# S7CAS-PLEIADES-CARTE-MERE_P20_Mechanical.net
KiCad netlist of a schematic drawn in Altium Designer
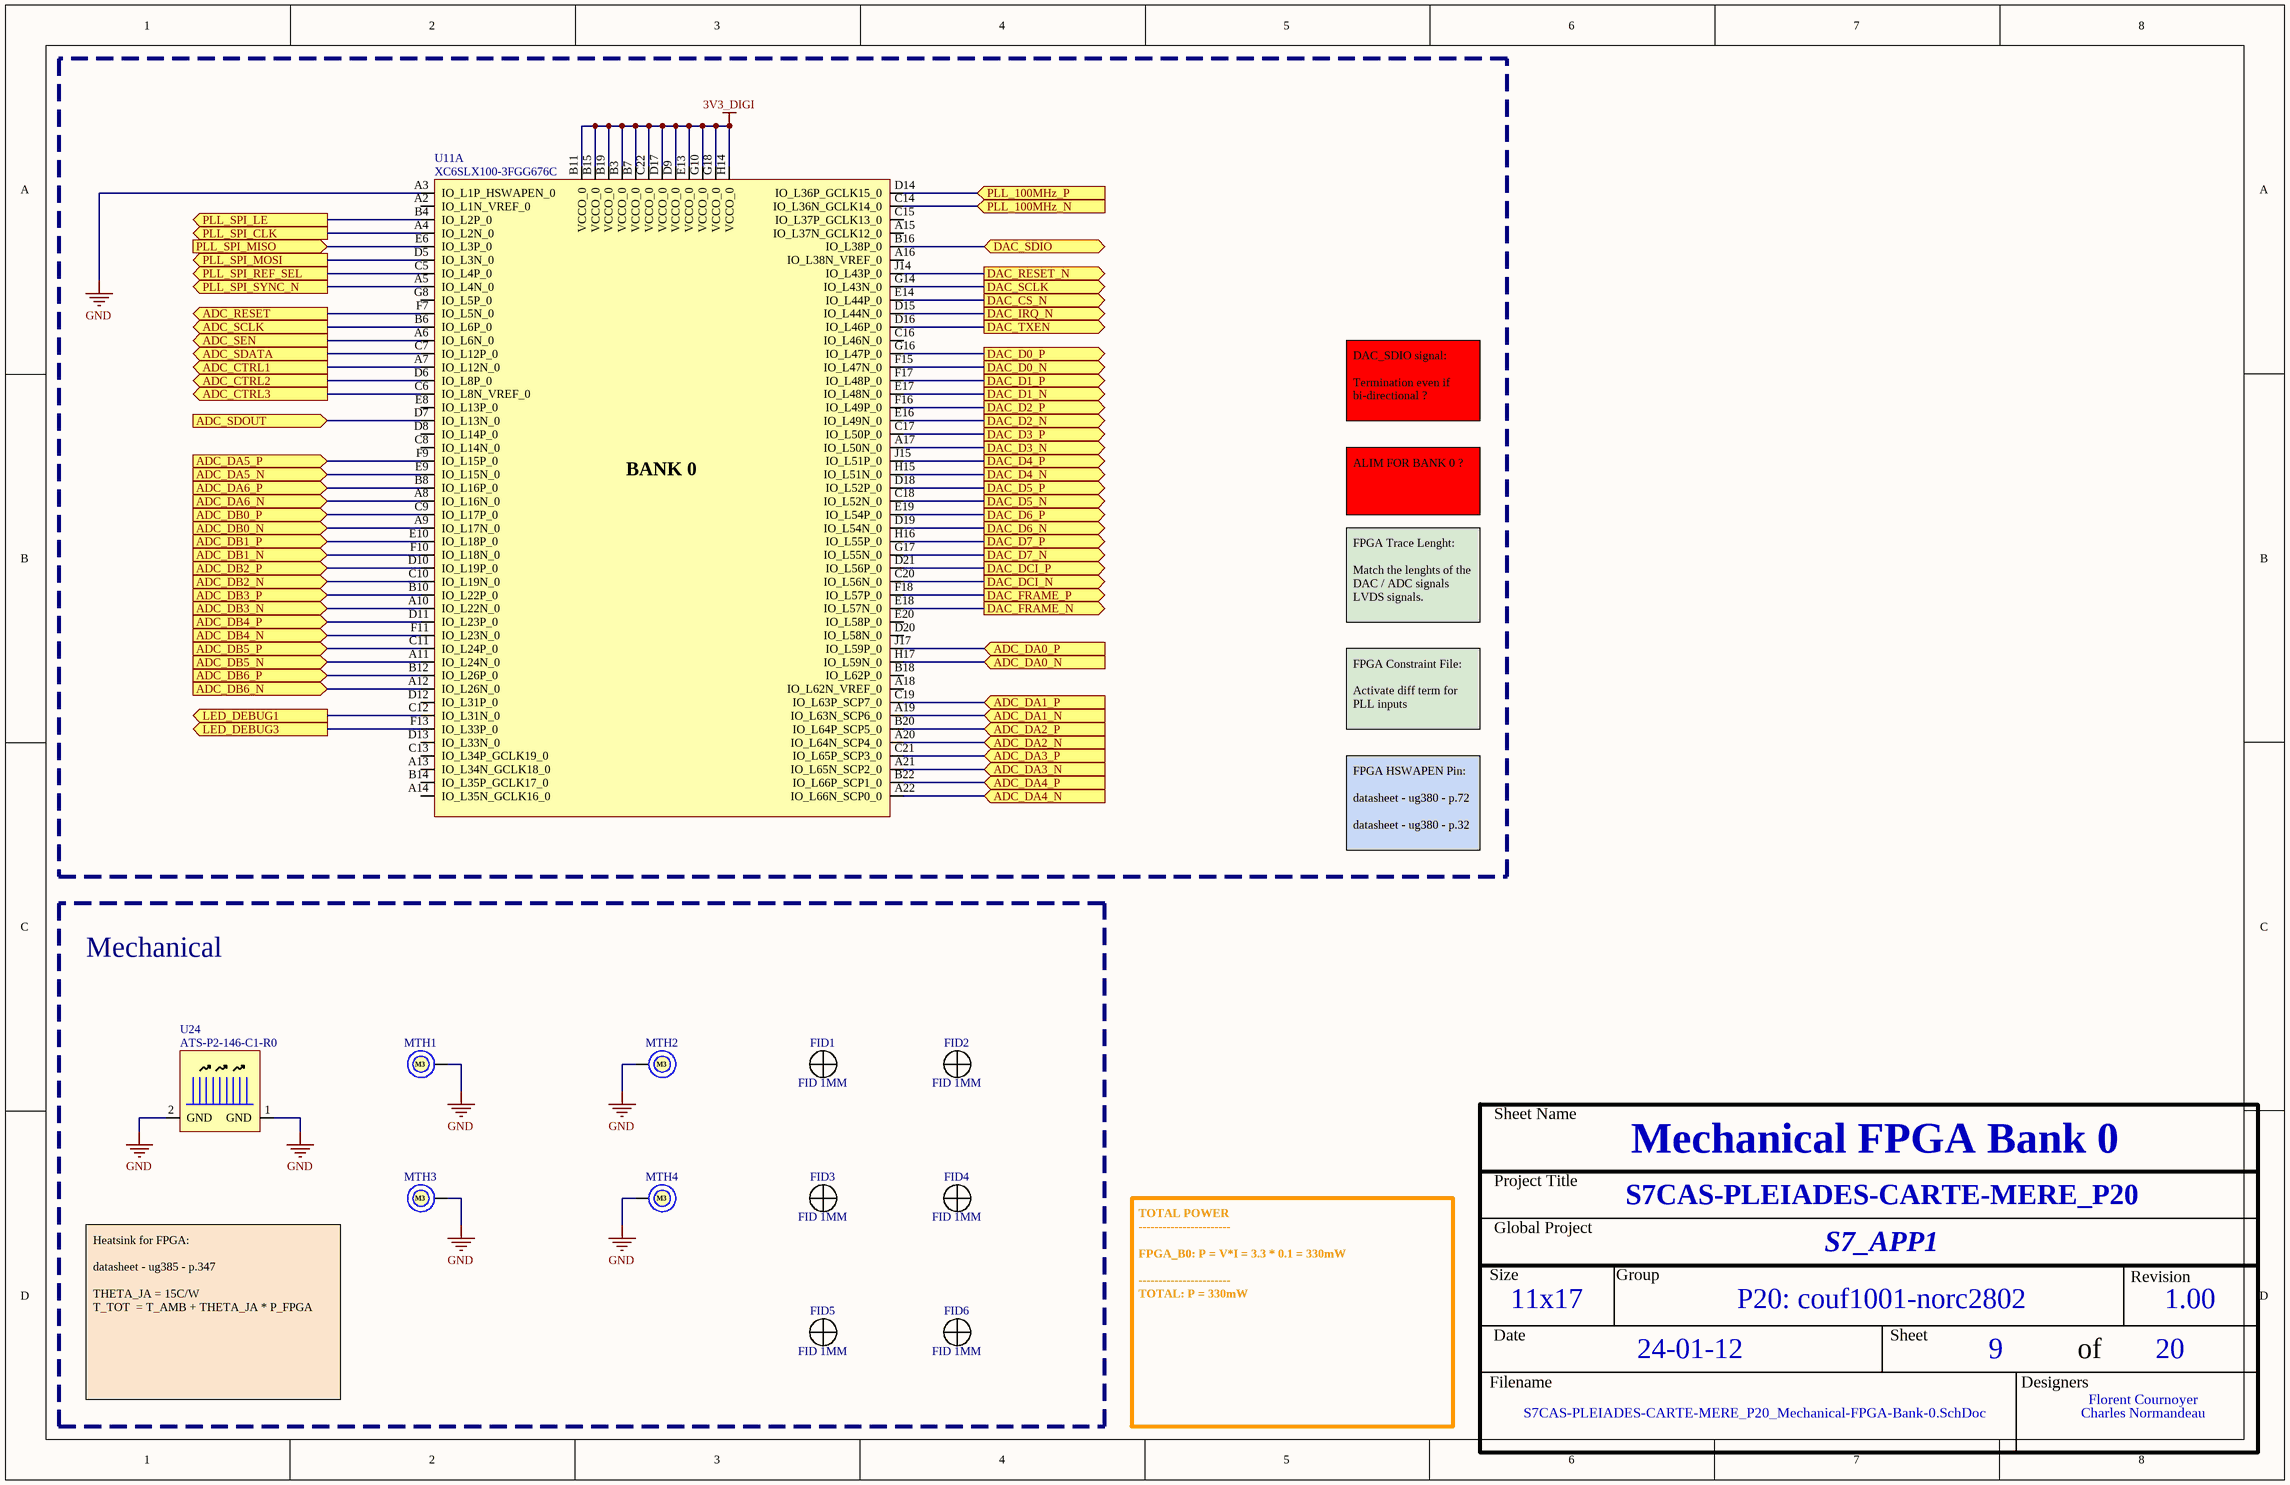
[diagram p0: S7CAS-PLEIADES-CARTE-MERE_P20_Mechanical-FPGA-Bank-0.SchDoc]

(export (version "E")
  (design (tool "Eeschema 10.0.6"))
  (components
    (comp (ref "FID1")
      (value "FID 1MM")
      (footprint "FID_CIRCLE_1MM")
      (description "FID - FIDUCIAL 1MM CIRCLE DOUBLE-SIDED - 1MM")
      (fields
        (field (name "CREATEDBY/DATE") "Jonathan Bouchard 2018-07-23")
        (field (name "VERIFIEDBY") "Caroline Paulin - 25 juillet 2018")
      )
      (libsource (lib "S7CAS_LIB2023") (part "FID_CIRCLE_1MM"))
    )
    (comp (ref "FID2")
      (value "FID 1MM")
      (footprint "FID_CIRCLE_1MM")
      (description "FID - FIDUCIAL 1MM CIRCLE DOUBLE-SIDED - 1MM")
      (fields
        (field (name "CREATEDBY/DATE") "Jonathan Bouchard 2018-07-23")
        (field (name "VERIFIEDBY") "Caroline Paulin - 25 juillet 2018")
      )
      (libsource (lib "S7CAS_LIB2023") (part "FID_CIRCLE_1MM"))
    )
    (comp (ref "FID3")
      (value "FID 1MM")
      (footprint "FID_CIRCLE_1MM")
      (description "FID - FIDUCIAL 1MM CIRCLE DOUBLE-SIDED - 1MM")
      (fields
        (field (name "CREATEDBY/DATE") "Jonathan Bouchard 2018-07-23")
        (field (name "VERIFIEDBY") "Caroline Paulin - 25 juillet 2018")
      )
      (libsource (lib "S7CAS_LIB2023") (part "FID_CIRCLE_1MM"))
    )
    (comp (ref "FID4")
      (value "FID 1MM")
      (footprint "FID_CIRCLE_1MM")
      (description "FID - FIDUCIAL 1MM CIRCLE DOUBLE-SIDED - 1MM")
      (fields
        (field (name "CREATEDBY/DATE") "Jonathan Bouchard 2018-07-23")
        (field (name "VERIFIEDBY") "Caroline Paulin - 25 juillet 2018")
      )
      (libsource (lib "S7CAS_LIB2023") (part "FID_CIRCLE_1MM"))
    )
    (comp (ref "FID5")
      (value "FID 1MM")
      (footprint "FID_CIRCLE_1MM")
      (description "FID - FIDUCIAL 1MM CIRCLE DOUBLE-SIDED - 1MM")
      (fields
        (field (name "CREATEDBY/DATE") "Jonathan Bouchard 2018-07-23")
        (field (name "VERIFIEDBY") "Caroline Paulin - 25 juillet 2018")
      )
      (libsource (lib "S7CAS_LIB2023") (part "FID_CIRCLE_1MM"))
    )
    (comp (ref "FID6")
      (value "FID 1MM")
      (footprint "FID_CIRCLE_1MM")
      (description "FID - FIDUCIAL 1MM CIRCLE DOUBLE-SIDED - 1MM")
      (fields
        (field (name "CREATEDBY/DATE") "Jonathan Bouchard 2018-07-23")
        (field (name "VERIFIEDBY") "Caroline Paulin - 25 juillet 2018")
      )
      (libsource (lib "S7CAS_LIB2023") (part "FID_CIRCLE_1MM"))
    )
    (comp (ref "MTH1")
      (value "M3")
      (footprint "MTH_M3")
      (description "MTH - MOUNTING HOLE M3 PLATED - M3")
      (fields
        (field (name "CREATEDBY/DATE") "Jonathan Bouchard 2018-07-23")
        (field (name "VERIFIEDBY") "Arnaud Samson 23-07-18")
      )
      (libsource (lib "S7CAS_LIB2023") (part "MTH_M3"))
    )
    (comp (ref "MTH2")
      (value "M3")
      (footprint "MTH_M3")
      (description "MTH - MOUNTING HOLE M3 PLATED - M3")
      (fields
        (field (name "CREATEDBY/DATE") "Jonathan Bouchard 2018-07-23")
        (field (name "VERIFIEDBY") "Arnaud Samson 23-07-18")
      )
      (libsource (lib "S7CAS_LIB2023") (part "MTH_M3"))
    )
    (comp (ref "MTH3")
      (value "M3")
      (footprint "MTH_M3")
      (description "MTH - MOUNTING HOLE M3 PLATED - M3")
      (fields
        (field (name "CREATEDBY/DATE") "Jonathan Bouchard 2018-07-23")
        (field (name "VERIFIEDBY") "Arnaud Samson 23-07-18")
      )
      (libsource (lib "S7CAS_LIB2023") (part "MTH_M3"))
    )
    (comp (ref "MTH4")
      (value "M3")
      (footprint "MTH_M3")
      (description "MTH - MOUNTING HOLE M3 PLATED - M3")
      (fields
        (field (name "CREATEDBY/DATE") "Jonathan Bouchard 2018-07-23")
        (field (name "VERIFIEDBY") "Arnaud Samson 23-07-18")
      )
      (libsource (lib "S7CAS_LIB2023") (part "MTH_M3"))
    )
    (comp (ref "U11")
      (value "XC6SLX100-3FGG676C")
      (footprint "FPGA_XILINX_FGG676")
      (description "FPGA - XILINX SPARTAN 6 480 I/O - BGA-676")
      (fields
        (field (name "VOLTAGE") "1.14 V ~ 1.26 V")
        (field (name "MFG") "Xilinx")
        (field (name "CREATEDBY") "Jonathan Bouchard")
      )
      (libsource (lib "S7CAS_LIB2023") (part "FPGA_XC6SLX100-3FGG676C"))
    )
    (comp (ref "U24")
      (value "ATS-P2-146-C1-R0")
      (footprint "HEATSINK")
      (description "HEATSINK 30X30X35MM L-TAB")
      (libsource (lib "LIB_TEMP_P20_CHARLES_NORMANDEAU_SCH") (part "HEATSINK"))
    )
  )
  (nets
    (net (code "1") (name "/ADC_CTRL1") (class "Default")
      (node (ref "U11") (pin "A7") (pinfunction "IO_L12N_0_A7") (pintype "passive"))
    )
    (net (code "2") (name "/ADC_CTRL2") (class "Default")
      (node (ref "U11") (pin "D6") (pinfunction "IO_L8P_0_D6") (pintype "passive"))
    )
    (net (code "3") (name "/ADC_CTRL3") (class "Default")
      (node (ref "U11") (pin "C6") (pinfunction "IO_L8N_VREF_0_C6") (pintype "passive"))
    )
    (net (code "4") (name "/ADC_DA0_N") (class "Default")
      (node (ref "U11") (pin "H17") (pinfunction "IO_L59N_0_H17") (pintype "passive"))
    )
    (net (code "5") (name "/ADC_DA0_P") (class "Default")
      (node (ref "U11") (pin "J17") (pinfunction "IO_L59P_0_J17") (pintype "passive"))
    )
    (net (code "6") (name "/ADC_DA1_N") (class "Default")
      (node (ref "U11") (pin "A19") (pinfunction "IO_L63N_SCP6_0_A19") (pintype "passive"))
    )
    (net (code "7") (name "/ADC_DA1_P") (class "Default")
      (node (ref "U11") (pin "C19") (pinfunction "IO_L63P_SCP7_0_C19") (pintype "passive"))
    )
    (net (code "8") (name "/ADC_DA2_N") (class "Default")
      (node (ref "U11") (pin "A20") (pinfunction "IO_L64N_SCP4_0_A20") (pintype "passive"))
    )
    (net (code "9") (name "/ADC_DA2_P") (class "Default")
      (node (ref "U11") (pin "B20") (pinfunction "IO_L64P_SCP5_0_B20") (pintype "passive"))
    )
    (net (code "10") (name "/ADC_DA3_N") (class "Default")
      (node (ref "U11") (pin "A21") (pinfunction "IO_L65N_SCP2_0_A21") (pintype "passive"))
    )
    (net (code "11") (name "/ADC_DA3_P") (class "Default")
      (node (ref "U11") (pin "C21") (pinfunction "IO_L65P_SCP3_0_C21") (pintype "passive"))
    )
    (net (code "12") (name "/ADC_DA4_N") (class "Default")
      (node (ref "U11") (pin "A22") (pinfunction "IO_L66N_SCP0_0_A22") (pintype "passive"))
    )
    (net (code "13") (name "/ADC_DA4_P") (class "Default")
      (node (ref "U11") (pin "B22") (pinfunction "IO_L66P_SCP1_0_B22") (pintype "passive"))
    )
    (net (code "14") (name "/ADC_DA5_N") (class "Default")
      (node (ref "U11") (pin "E9") (pinfunction "IO_L15N_0_E9") (pintype "passive"))
    )
    (net (code "15") (name "/ADC_DA5_P") (class "Default")
      (node (ref "U11") (pin "F9") (pinfunction "IO_L15P_0_F9") (pintype "passive"))
    )
    (net (code "16") (name "/ADC_DA6_N") (class "Default")
      (node (ref "U11") (pin "A8") (pinfunction "IO_L16N_0_A8") (pintype "passive"))
    )
    (net (code "17") (name "/ADC_DA6_P") (class "Default")
      (node (ref "U11") (pin "B8") (pinfunction "IO_L16P_0_B8") (pintype "passive"))
    )
    (net (code "18") (name "/ADC_DB0_N") (class "Default")
      (node (ref "U11") (pin "A9") (pinfunction "IO_L17N_0_A9") (pintype "passive"))
    )
    (net (code "19") (name "/ADC_DB0_P") (class "Default")
      (node (ref "U11") (pin "C9") (pinfunction "IO_L17P_0_C9") (pintype "passive"))
    )
    (net (code "20") (name "/ADC_DB1_N") (class "Default")
      (node (ref "U11") (pin "F10") (pinfunction "IO_L18N_0_F10") (pintype "passive"))
    )
    (net (code "21") (name "/ADC_DB1_P") (class "Default")
      (node (ref "U11") (pin "E10") (pinfunction "IO_L18P_0_E10") (pintype "passive"))
    )
    (net (code "22") (name "/ADC_DB2_N") (class "Default")
      (node (ref "U11") (pin "C10") (pinfunction "IO_L19N_0_C10") (pintype "passive"))
    )
    (net (code "23") (name "/ADC_DB2_P") (class "Default")
      (node (ref "U11") (pin "D10") (pinfunction "IO_L19P_0_D10") (pintype "passive"))
    )
    (net (code "24") (name "/ADC_DB3_N") (class "Default")
      (node (ref "U11") (pin "A10") (pinfunction "IO_L22N_0_A10") (pintype "passive"))
    )
    (net (code "25") (name "/ADC_DB3_P") (class "Default")
      (node (ref "U11") (pin "B10") (pinfunction "IO_L22P_0_B10") (pintype "passive"))
    )
    (net (code "26") (name "/ADC_DB4_N") (class "Default")
      (node (ref "U11") (pin "F11") (pinfunction "IO_L23N_0_F11") (pintype "passive"))
    )
    (net (code "27") (name "/ADC_DB4_P") (class "Default")
      (node (ref "U11") (pin "D11") (pinfunction "IO_L23P_0_D11") (pintype "passive"))
    )
    (net (code "28") (name "/ADC_DB5_N") (class "Default")
      (node (ref "U11") (pin "A11") (pinfunction "IO_L24N_0_A11") (pintype "passive"))
    )
    (net (code "29") (name "/ADC_DB5_P") (class "Default")
      (node (ref "U11") (pin "C11") (pinfunction "IO_L24P_0_C11") (pintype "passive"))
    )
    (net (code "30") (name "/ADC_DB6_N") (class "Default")
      (node (ref "U11") (pin "A12") (pinfunction "IO_L26N_0_A12") (pintype "passive"))
    )
    (net (code "31") (name "/ADC_DB6_P") (class "Default")
      (node (ref "U11") (pin "B12") (pinfunction "IO_L26P_0_B12") (pintype "passive"))
    )
    (net (code "32") (name "/ADC_RESET") (class "Default")
      (node (ref "U11") (pin "F7") (pinfunction "IO_L5N_0_F7") (pintype "passive"))
    )
    (net (code "33") (name "/ADC_SCLK") (class "Default")
      (node (ref "U11") (pin "B6") (pinfunction "IO_L6P_0_B6") (pintype "passive"))
    )
    (net (code "34") (name "/ADC_SDATA") (class "Default")
      (node (ref "U11") (pin "C7") (pinfunction "IO_L12P_0_C7") (pintype "passive"))
    )
    (net (code "35") (name "/ADC_SDOUT") (class "Default")
      (node (ref "U11") (pin "D7") (pinfunction "IO_L13N_0_D7") (pintype "passive"))
    )
    (net (code "36") (name "/ADC_SEN") (class "Default")
      (node (ref "U11") (pin "A6") (pinfunction "IO_L6N_0_A6") (pintype "passive"))
    )
    (net (code "37") (name "/DAC_CS_N") (class "Default")
      (node (ref "U11") (pin "E14") (pinfunction "IO_L44P_0_E14") (pintype "passive"))
    )
    (net (code "38") (name "/DAC_D0_N") (class "Default")
      (node (ref "U11") (pin "F15") (pinfunction "IO_L47N_0_F15") (pintype "passive"))
    )
    (net (code "39") (name "/DAC_D0_P") (class "Default")
      (node (ref "U11") (pin "G16") (pinfunction "IO_L47P_0_G16") (pintype "passive"))
    )
    (net (code "40") (name "/DAC_D1_N") (class "Default")
      (node (ref "U11") (pin "E17") (pinfunction "IO_L48N_0_E17") (pintype "passive"))
    )
    (net (code "41") (name "/DAC_D1_P") (class "Default")
      (node (ref "U11") (pin "F17") (pinfunction "IO_L48P_0_F17") (pintype "passive"))
    )
    (net (code "42") (name "/DAC_D2_N") (class "Default")
      (node (ref "U11") (pin "E16") (pinfunction "IO_L49N_0_E16") (pintype "passive"))
    )
    (net (code "43") (name "/DAC_D2_P") (class "Default")
      (node (ref "U11") (pin "F16") (pinfunction "IO_L49P_0_F16") (pintype "passive"))
    )
    (net (code "44") (name "/DAC_D3_N") (class "Default")
      (node (ref "U11") (pin "A17") (pinfunction "IO_L50N_0_A17") (pintype "passive"))
    )
    (net (code "45") (name "/DAC_D3_P") (class "Default")
      (node (ref "U11") (pin "C17") (pinfunction "IO_L50P_0_C17") (pintype "passive"))
    )
    (net (code "46") (name "/DAC_D4_N") (class "Default")
      (node (ref "U11") (pin "H15") (pinfunction "IO_L51N_0_H15") (pintype "passive"))
    )
    (net (code "47") (name "/DAC_D4_P") (class "Default")
      (node (ref "U11") (pin "J15") (pinfunction "IO_L51P_0_J15") (pintype "passive"))
    )
    (net (code "48") (name "/DAC_D5_N") (class "Default")
      (node (ref "U11") (pin "C18") (pinfunction "IO_L52N_0_C18") (pintype "passive"))
    )
    (net (code "49") (name "/DAC_D5_P") (class "Default")
      (node (ref "U11") (pin "D18") (pinfunction "IO_L52P_0_D18") (pintype "passive"))
    )
    (net (code "50") (name "/DAC_D6_N") (class "Default")
      (node (ref "U11") (pin "D19") (pinfunction "IO_L54N_0_D19") (pintype "passive"))
    )
    (net (code "51") (name "/DAC_D6_P") (class "Default")
      (node (ref "U11") (pin "E19") (pinfunction "IO_L54P_0_E19") (pintype "passive"))
    )
    (net (code "52") (name "/DAC_D7_N") (class "Default")
      (node (ref "U11") (pin "G17") (pinfunction "IO_L55N_0_G17") (pintype "passive"))
    )
    (net (code "53") (name "/DAC_D7_P") (class "Default")
      (node (ref "U11") (pin "H16") (pinfunction "IO_L55P_0_H16") (pintype "passive"))
    )
    (net (code "54") (name "/DAC_DCI_N") (class "Default")
      (node (ref "U11") (pin "C20") (pinfunction "IO_L56N_0_C20") (pintype "passive"))
    )
    (net (code "55") (name "/DAC_DCI_P") (class "Default")
      (node (ref "U11") (pin "D21") (pinfunction "IO_L56P_0_D21") (pintype "passive"))
    )
    (net (code "56") (name "/DAC_FRAME_N") (class "Default")
      (node (ref "U11") (pin "E18") (pinfunction "IO_L57N_0_E18") (pintype "passive"))
    )
    (net (code "57") (name "/DAC_FRAME_P") (class "Default")
      (node (ref "U11") (pin "F18") (pinfunction "IO_L57P_0_F18") (pintype "passive"))
    )
    (net (code "58") (name "/DAC_IRQ_N") (class "Default")
      (node (ref "U11") (pin "D15") (pinfunction "IO_L44N_0_D15") (pintype "passive"))
    )
    (net (code "59") (name "/DAC_RESET_N") (class "Default")
      (node (ref "U11") (pin "J14") (pinfunction "IO_L43P_0_J14") (pintype "passive"))
    )
    (net (code "60") (name "/DAC_SCLK") (class "Default")
      (node (ref "U11") (pin "G14") (pinfunction "IO_L43N_0_G14") (pintype "passive"))
    )
    (net (code "61") (name "/DAC_SDIO") (class "Default")
      (node (ref "U11") (pin "B16") (pinfunction "IO_L38P_0_B16") (pintype "passive"))
    )
    (net (code "62") (name "/DAC_TXEN") (class "Default")
      (node (ref "U11") (pin "D16") (pinfunction "IO_L46P_0_D16") (pintype "passive"))
    )
    (net (code "63") (name "/LED_DEBUG1") (class "Default")
      (node (ref "U11") (pin "C12") (pinfunction "IO_L31N_0_C12") (pintype "passive"))
    )
    (net (code "64") (name "/LED_DEBUG3") (class "Default")
      (node (ref "U11") (pin "F13") (pinfunction "IO_L33P_0_F13") (pintype "passive"))
    )
    (net (code "65") (name "/PLL_100MHz_N") (class "Default")
      (node (ref "U11") (pin "C14") (pinfunction "IO_L36N_GCLK14_0_C14") (pintype "passive"))
    )
    (net (code "66") (name "/PLL_100MHz_P") (class "Default")
      (node (ref "U11") (pin "D14") (pinfunction "IO_L36P_GCLK15_0_D14") (pintype "passive"))
    )
    (net (code "67") (name "/PLL_SPI_CLK") (class "Default")
      (node (ref "U11") (pin "A4") (pinfunction "IO_L2N_0_A4") (pintype "passive"))
    )
    (net (code "68") (name "/PLL_SPI_LE") (class "Default")
      (node (ref "U11") (pin "B4") (pinfunction "IO_L2P_0_B4") (pintype "passive"))
    )
    (net (code "69") (name "/PLL_SPI_MISO") (class "Default")
      (node (ref "U11") (pin "E6") (pinfunction "IO_L3P_0_E6") (pintype "passive"))
    )
    (net (code "70") (name "/PLL_SPI_MOSI") (class "Default")
      (node (ref "U11") (pin "D5") (pinfunction "IO_L3N_0_D5") (pintype "passive"))
    )
    (net (code "71") (name "/PLL_SPI_REF_SEL") (class "Default")
      (node (ref "U11") (pin "C5") (pinfunction "IO_L4P_0_C5") (pintype "passive"))
    )
    (net (code "72") (name "/PLL_SPI_SYNC_N") (class "Default")
      (node (ref "U11") (pin "A5") (pinfunction "IO_L4N_0_A5") (pintype "passive"))
    )
    (net (code "73") (name "3V3_DIGI") (class "Default")
      (node (ref "U11") (pin "B11") (pinfunction "VCCO_0_B11") (pintype "passive"))
      (node (ref "U11") (pin "B15") (pinfunction "VCCO_0_B15") (pintype "passive"))
      (node (ref "U11") (pin "B19") (pinfunction "VCCO_0_B19") (pintype "passive"))
      (node (ref "U11") (pin "B3") (pinfunction "VCCO_0_B3") (pintype "passive"))
      (node (ref "U11") (pin "B7") (pinfunction "VCCO_0_B7") (pintype "passive"))
      (node (ref "U11") (pin "C22") (pinfunction "VCCO_0_C22") (pintype "passive"))
      (node (ref "U11") (pin "D17") (pinfunction "VCCO_0_D17") (pintype "passive"))
      (node (ref "U11") (pin "D9") (pinfunction "VCCO_0_D9") (pintype "passive"))
      (node (ref "U11") (pin "E13") (pinfunction "VCCO_0_E13") (pintype "passive"))
      (node (ref "U11") (pin "G10") (pinfunction "VCCO_0_G10") (pintype "passive"))
      (node (ref "U11") (pin "G18") (pinfunction "VCCO_0_G18") (pintype "passive"))
      (node (ref "U11") (pin "H14") (pinfunction "VCCO_0_H14") (pintype "passive"))
    )
    (net (code "74") (name "GND") (class "Default")
      (node (ref "MTH1") (pin "1") (pinfunction "1_1") (pintype "passive"))
      (node (ref "MTH2") (pin "1") (pinfunction "1_1") (pintype "passive"))
      (node (ref "MTH3") (pin "1") (pinfunction "1_1") (pintype "passive"))
      (node (ref "MTH4") (pin "1") (pinfunction "1_1") (pintype "passive"))
      (node (ref "U11") (pin "A3") (pinfunction "IO_L1P_HSWAPEN_0_A3") (pintype "passive"))
      (node (ref "U24") (pin "1") (pinfunction "GND_1") (pintype "passive"))
      (node (ref "U24") (pin "2") (pinfunction "GND_2") (pintype "passive"))
    )
    (net (code "75") (name "unconnected-(FID1-Pad1)") (class "Default")
      (node (ref "FID1") (pin "1") (pinfunction "1_1") (pintype "passive"))
    )
    (net (code "76") (name "unconnected-(FID1-Pad2)") (class "Default")
      (node (ref "FID1") (pin "2") (pinfunction "2_2") (pintype "passive"))
    )
    (net (code "77") (name "unconnected-(FID2-Pad1)") (class "Default")
      (node (ref "FID2") (pin "1") (pinfunction "1_1") (pintype "passive"))
    )
    (net (code "78") (name "unconnected-(FID2-Pad2)") (class "Default")
      (node (ref "FID2") (pin "2") (pinfunction "2_2") (pintype "passive"))
    )
    (net (code "79") (name "unconnected-(FID3-Pad1)") (class "Default")
      (node (ref "FID3") (pin "1") (pinfunction "1_1") (pintype "passive"))
    )
    (net (code "80") (name "unconnected-(FID3-Pad2)") (class "Default")
      (node (ref "FID3") (pin "2") (pinfunction "2_2") (pintype "passive"))
    )
    (net (code "81") (name "unconnected-(FID4-Pad1)") (class "Default")
      (node (ref "FID4") (pin "1") (pinfunction "1_1") (pintype "passive"))
    )
    (net (code "82") (name "unconnected-(FID4-Pad2)") (class "Default")
      (node (ref "FID4") (pin "2") (pinfunction "2_2") (pintype "passive"))
    )
    (net (code "83") (name "unconnected-(FID5-Pad1)") (class "Default")
      (node (ref "FID5") (pin "1") (pinfunction "1_1") (pintype "passive"))
    )
    (net (code "84") (name "unconnected-(FID5-Pad2)") (class "Default")
      (node (ref "FID5") (pin "2") (pinfunction "2_2") (pintype "passive"))
    )
    (net (code "85") (name "unconnected-(FID6-Pad1)") (class "Default")
      (node (ref "FID6") (pin "1") (pinfunction "1_1") (pintype "passive"))
    )
    (net (code "86") (name "unconnected-(FID6-Pad2)") (class "Default")
      (node (ref "FID6") (pin "2") (pinfunction "2_2") (pintype "passive"))
    )
    (net (code "87") (name "unconnected-(U11A-IO_L1N_VREF_0-PadA2)") (class "Default")
      (node (ref "U11") (pin "A2") (pinfunction "IO_L1N_VREF_0_A2") (pintype "passive"))
    )
    (net (code "88") (name "unconnected-(U11A-IO_L5P_0-PadG8)") (class "Default")
      (node (ref "U11") (pin "G8") (pinfunction "IO_L5P_0_G8") (pintype "passive"))
    )
    (net (code "89") (name "unconnected-(U11A-IO_L13P_0-PadE8)") (class "Default")
      (node (ref "U11") (pin "E8") (pinfunction "IO_L13P_0_E8") (pintype "passive"))
    )
    (net (code "90") (name "unconnected-(U11A-IO_L14N_0-PadC8)") (class "Default")
      (node (ref "U11") (pin "C8") (pinfunction "IO_L14N_0_C8") (pintype "passive"))
    )
    (net (code "91") (name "unconnected-(U11A-IO_L14P_0-PadD8)") (class "Default")
      (node (ref "U11") (pin "D8") (pinfunction "IO_L14P_0_D8") (pintype "passive"))
    )
    (net (code "92") (name "unconnected-(U11A-IO_L31P_0-PadD12)") (class "Default")
      (node (ref "U11") (pin "D12") (pinfunction "IO_L31P_0_D12") (pintype "passive"))
    )
    (net (code "93") (name "unconnected-(U11A-IO_L33N_0-PadD13)") (class "Default")
      (node (ref "U11") (pin "D13") (pinfunction "IO_L33N_0_D13") (pintype "passive"))
    )
    (net (code "94") (name "unconnected-(U11A-IO_L34N_GCLK18_0-PadA13)") (class "Default")
      (node (ref "U11") (pin "A13") (pinfunction "IO_L34N_GCLK18_0_A13") (pintype "passive"))
    )
    (net (code "95") (name "unconnected-(U11A-IO_L34P_GCLK19_0-PadC13)") (class "Default")
      (node (ref "U11") (pin "C13") (pinfunction "IO_L34P_GCLK19_0_C13") (pintype "passive"))
    )
    (net (code "96") (name "unconnected-(U11A-IO_L35N_GCLK16_0-PadA14)") (class "Default")
      (node (ref "U11") (pin "A14") (pinfunction "IO_L35N_GCLK16_0_A14") (pintype "passive"))
    )
    (net (code "97") (name "unconnected-(U11A-IO_L35P_GCLK17_0-PadB14)") (class "Default")
      (node (ref "U11") (pin "B14") (pinfunction "IO_L35P_GCLK17_0_B14") (pintype "passive"))
    )
    (net (code "98") (name "unconnected-(U11A-IO_L37N_GCLK12_0-PadA15)") (class "Default")
      (node (ref "U11") (pin "A15") (pinfunction "IO_L37N_GCLK12_0_A15") (pintype "passive"))
    )
    (net (code "99") (name "unconnected-(U11A-IO_L37P_GCLK13_0-PadC15)") (class "Default")
      (node (ref "U11") (pin "C15") (pinfunction "IO_L37P_GCLK13_0_C15") (pintype "passive"))
    )
    (net (code "100") (name "unconnected-(U11A-IO_L38N_VREF_0-PadA16)") (class "Default")
      (node (ref "U11") (pin "A16") (pinfunction "IO_L38N_VREF_0_A16") (pintype "passive"))
    )
    (net (code "101") (name "unconnected-(U11A-IO_L46N_0-PadC16)") (class "Default")
      (node (ref "U11") (pin "C16") (pinfunction "IO_L46N_0_C16") (pintype "passive"))
    )
    (net (code "102") (name "unconnected-(U11A-IO_L58N_0-PadD20)") (class "Default")
      (node (ref "U11") (pin "D20") (pinfunction "IO_L58N_0_D20") (pintype "passive"))
    )
    (net (code "103") (name "unconnected-(U11A-IO_L58P_0-PadE20)") (class "Default")
      (node (ref "U11") (pin "E20") (pinfunction "IO_L58P_0_E20") (pintype "passive"))
    )
    (net (code "104") (name "unconnected-(U11A-IO_L62N_VREF_0-PadA18)") (class "Default")
      (node (ref "U11") (pin "A18") (pinfunction "IO_L62N_VREF_0_A18") (pintype "passive"))
    )
    (net (code "105") (name "unconnected-(U11A-IO_L62P_0-PadB18)") (class "Default")
      (node (ref "U11") (pin "B18") (pinfunction "IO_L62P_0_B18") (pintype "passive"))
    )
  )
)
